# CA2832_simple.net
KiCad netlist of a schematic drawn in EAGLE
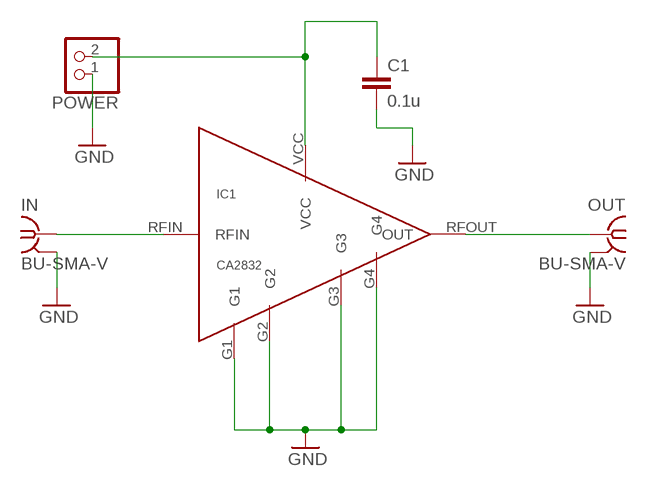
[diagram p0: schematic, sheet 1]

(export (version "E")
  (design (tool "Eeschema 10.0.6"))
  (components
    (comp (ref "C1")
      (value "0.1u")
      (footprint "eagle-import:C1206")
      (libsource (lib "eagle-import") (part "C-EUC1206"))
    )
    (comp (ref "IC1")
      (value "CA2832")
      (footprint "eagle-import:714F-03")
      (libsource (lib "eagle-import") (part "CA2832"))
    )
    (comp (ref "IN")
      (value "BU-SMA-V")
      (footprint "eagle-import:BU-SMA-V")
      (libsource (lib "eagle-import") (part "BU-SMA-V"))
    )
    (comp (ref "OUT")
      (value "BU-SMA-V")
      (footprint "eagle-import:BU-SMA-V")
      (libsource (lib "eagle-import") (part "BU-SMA-V"))
    )
    (comp (ref "POWER")
      (value "PINHD-1X2")
      (footprint "eagle-import:1X02")
      (libsource (lib "eagle-import") (part "PINHD-1X2"))
    )
  )
  (nets
    (net (code "1") (name "GND") (class "Default")
      (node (ref "C1") (pin "2") (pinfunction "2_2") (pintype "passive"))
      (node (ref "IC1") (pin "G1") (pinfunction "G1_G1") (pintype "power_in"))
      (node (ref "IC1") (pin "G2") (pinfunction "G2_G2") (pintype "power_in"))
      (node (ref "IC1") (pin "G3") (pinfunction "G3_G3") (pintype "power_in"))
      (node (ref "IC1") (pin "G4") (pinfunction "G4_G4") (pintype "power_in"))
      (node (ref "IN") (pin "2") (pinfunction "2_2") (pintype "passive"))
      (node (ref "IN") (pin "3") (pinfunction "2_3") (pintype "passive"))
      (node (ref "IN") (pin "4") (pinfunction "2_4") (pintype "passive"))
      (node (ref "IN") (pin "5") (pinfunction "2_5") (pintype "passive"))
      (node (ref "OUT") (pin "2") (pinfunction "2_2") (pintype "passive"))
      (node (ref "OUT") (pin "3") (pinfunction "2_3") (pintype "passive"))
      (node (ref "OUT") (pin "4") (pinfunction "2_4") (pintype "passive"))
      (node (ref "OUT") (pin "5") (pinfunction "2_5") (pintype "passive"))
      (node (ref "POWER") (pin "1") (pinfunction "1_1") (pintype "passive"))
    )
    (net (code "2") (name "Net-(C1-Pad1)") (class "Default")
      (node (ref "C1") (pin "1") (pinfunction "1_1") (pintype "passive"))
      (node (ref "IC1") (pin "VCC") (pinfunction "VCC_VCC") (pintype "power_in"))
      (node (ref "POWER") (pin "2") (pinfunction "2_2") (pintype "passive"))
    )
    (net (code "3") (name "Net-(IC1-OUT)") (class "Default")
      (node (ref "IC1") (pin "RFOUT") (pinfunction "OUT_RFOUT") (pintype "output"))
      (node (ref "OUT") (pin "1") (pinfunction "1_1") (pintype "passive"))
    )
    (net (code "4") (name "Net-(IC1-PadRFIN)") (class "Default")
      (node (ref "IC1") (pin "RFIN") (pinfunction "RFIN_RFIN") (pintype "input"))
      (node (ref "IN") (pin "1") (pinfunction "1_1") (pintype "passive"))
    )
  )
)
